# VCA.net
KiCad netlist of a schematic drawn in Altium Designer
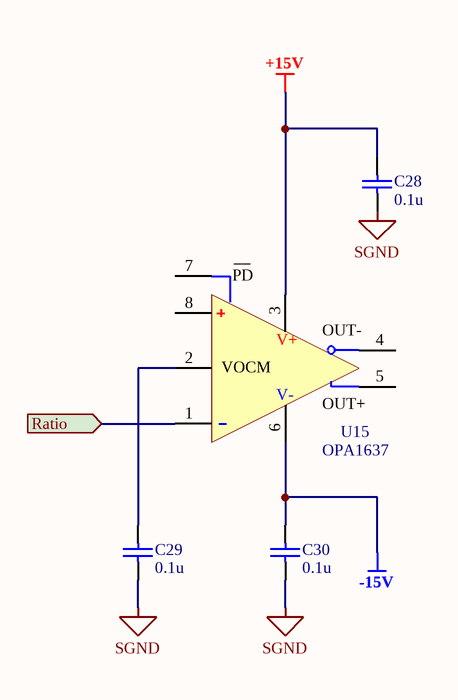
[diagram p0: VCA.SchDoc]

(export (version "E")
  (design (tool "Eeschema 10.0.6"))
  (components
    (comp (ref "C28")
      (value "0.1u")
      (description "Capacitor")
      (libsource (lib "Simulation Generic Components") (part "Capacitor"))
    )
    (comp (ref "C29")
      (value "0.1u")
      (description "Capacitor")
      (libsource (lib "Simulation Generic Components") (part "Capacitor"))
    )
    (comp (ref "C30")
      (value "0.1u")
      (description "Capacitor")
      (libsource (lib "Simulation Generic Components") (part "Capacitor"))
    )
    (comp (ref "U15")
      (value "OPA1637")
      (footprint "FP-DGK0008A-IPC_A")
      (description "Fully differential amplifier")
      (libsource (lib "DRC") (part "OPA1637DGKT"))
    )
  )
  (nets
    (net (code "1") (name "+15V") (class "Default")
      (node (ref "C28") (pin "2") (pinfunction "2_2") (pintype "passive"))
      (node (ref "U15") (pin "3") (pinfunction "VS+_3") (pintype "power_in"))
    )
    (net (code "2") (name "-15V") (class "Default")
      (node (ref "C30") (pin "2") (pinfunction "2_2") (pintype "passive"))
      (node (ref "U15") (pin "6") (pinfunction "VS-_6") (pintype "power_in"))
    )
    (net (code "3") (name "/Ratio") (class "Default")
      (node (ref "U15") (pin "1") (pinfunction "IN-_1") (pintype "tri_state"))
    )
    (net (code "4") (name "Net-(U15-VOCM)") (class "Default")
      (node (ref "C29") (pin "2") (pinfunction "2_2") (pintype "passive"))
      (node (ref "U15") (pin "2") (pinfunction "VOCM_2") (pintype "power_in"))
    )
    (net (code "5") (name "SGND") (class "Default")
      (node (ref "C28") (pin "1") (pinfunction "1_1") (pintype "passive"))
      (node (ref "C29") (pin "1") (pinfunction "1_1") (pintype "passive"))
      (node (ref "C30") (pin "1") (pinfunction "1_1") (pintype "passive"))
    )
    (net (code "6") (name "unconnected-(U15-IN+-Pad8)") (class "Default")
      (node (ref "U15") (pin "8") (pinfunction "IN+_8") (pintype "tri_state"))
    )
    (net (code "7") (name "unconnected-(U15-OUT+-Pad4)") (class "Default")
      (node (ref "U15") (pin "4") (pinfunction "OUT+_4") (pintype "passive"))
    )
    (net (code "8") (name "unconnected-(U15-OUT--Pad5)") (class "Default")
      (node (ref "U15") (pin "5") (pinfunction "OUT-_5") (pintype "passive"))
    )
    (net (code "9") (name "unconnected-(U15-~{PD}-Pad7)") (class "Default")
      (node (ref "U15") (pin "7") (pinfunction "~{PD}_7") (pintype "open_collector"))
    )
  )
)
